# T11-MIDITheremin.net
KiCad netlist of a schematic drawn in EAGLE
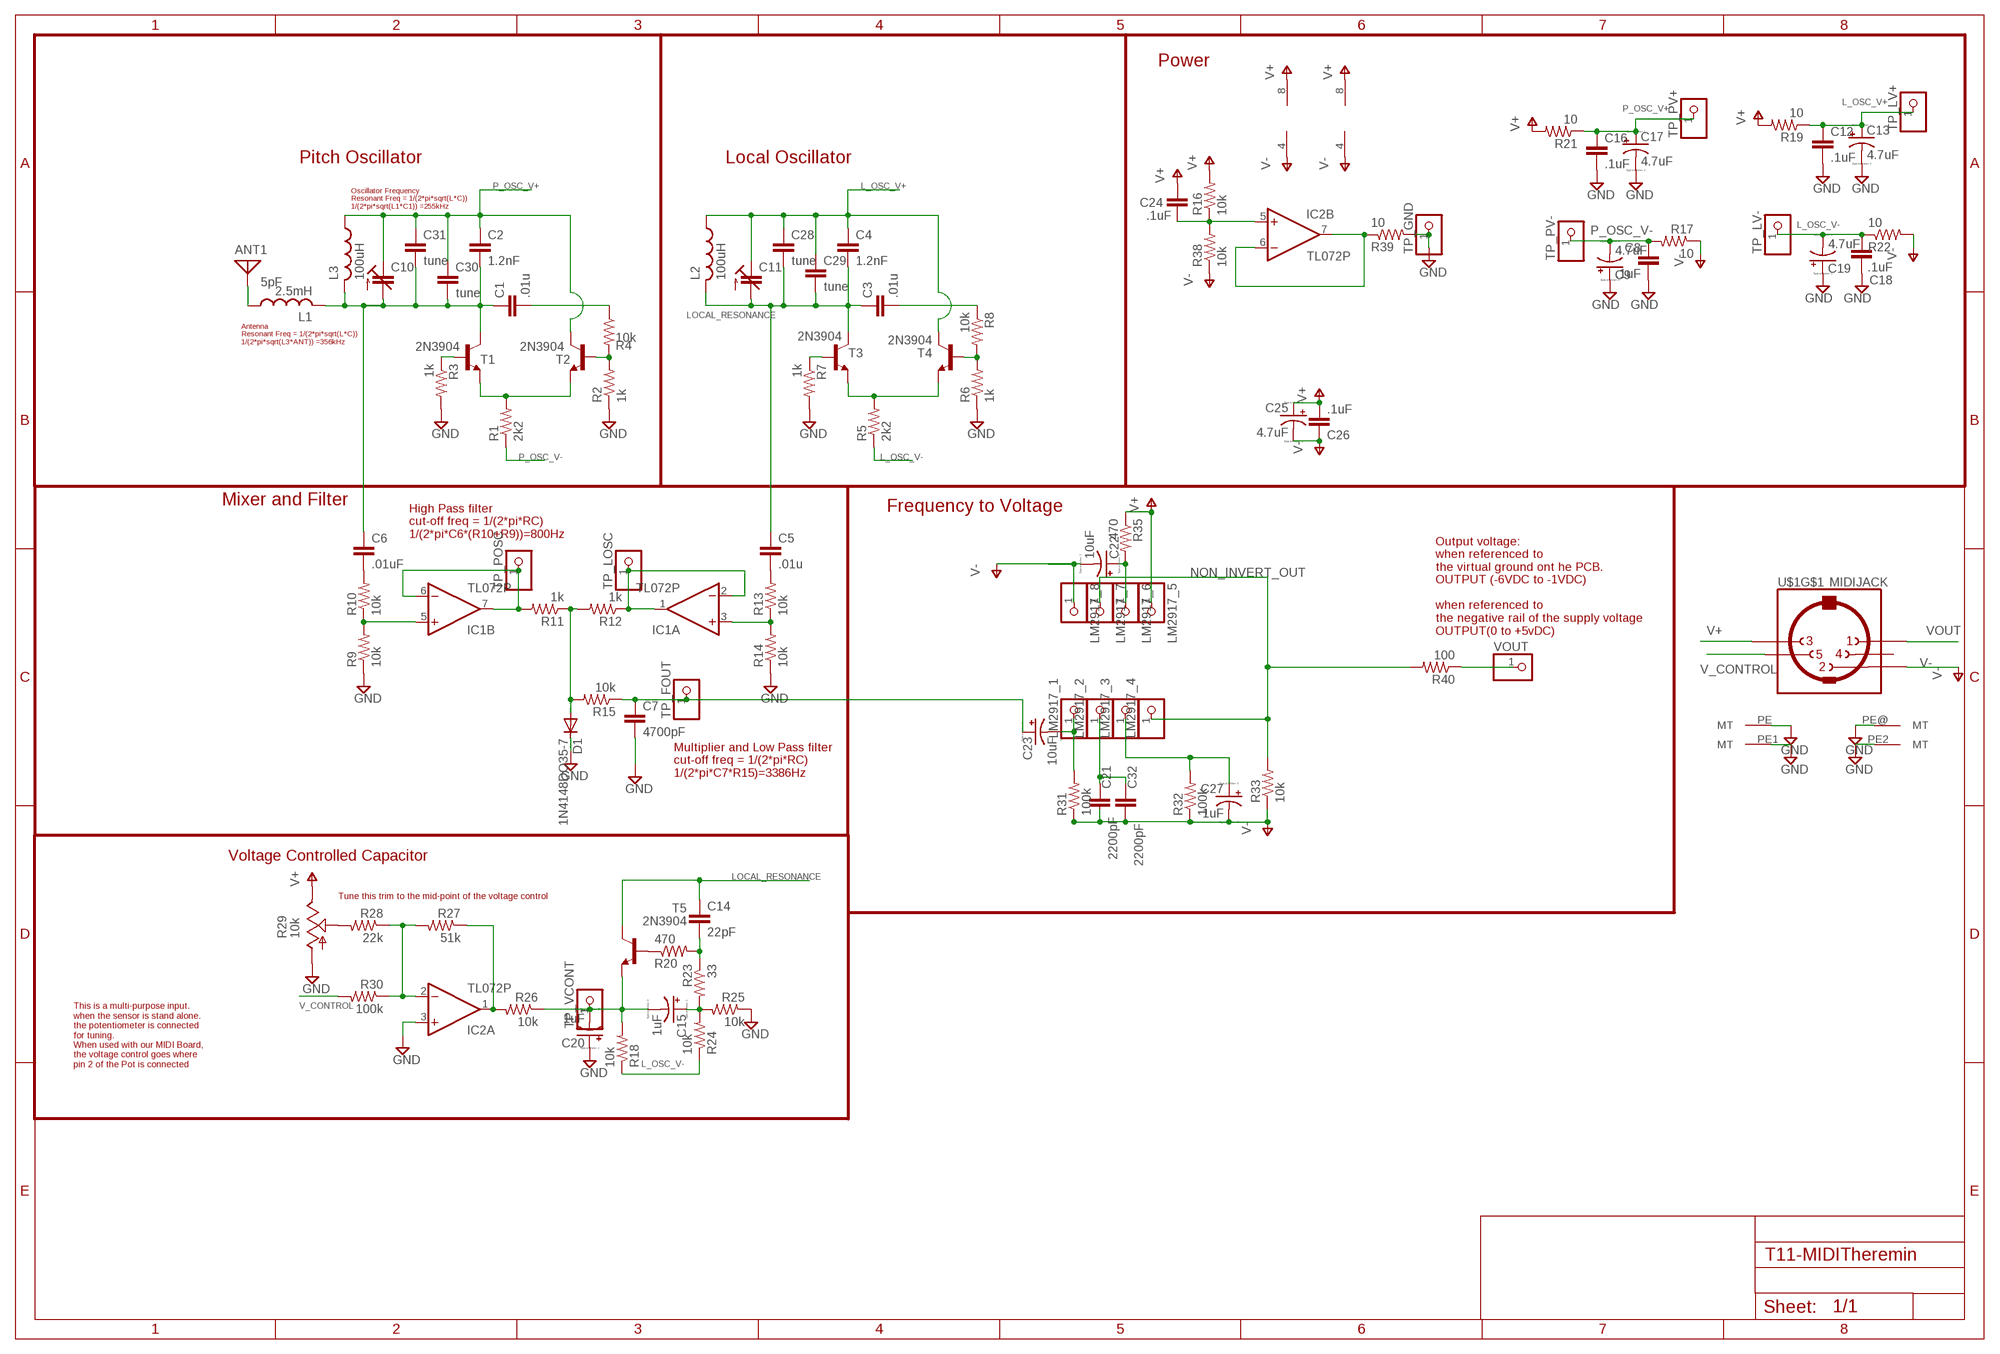
[diagram p0: schematic, sheet 1]

(export (version "E")
  (design (tool "Eeschema 10.0.6"))
  (components
    (comp (ref "ANT1")
      (value "5pF")
      (footprint "eagle-import:PAD-01")
      (libsource (lib "eagle-import") (part "ANTENNA"))
    )
    (comp (ref "C1")
      (value ".01u")
      (footprint "eagle-import:C050-025X075")
      (libsource (lib "eagle-import") (part "C-EU050-025X075"))
    )
    (comp (ref "C2")
      (value "1.2nF")
      (footprint "eagle-import:C050-025X075")
      (libsource (lib "eagle-import") (part "C-EU050-025X075"))
    )
    (comp (ref "C3")
      (value ".01u")
      (footprint "eagle-import:C050-025X075")
      (libsource (lib "eagle-import") (part "C-EU050-025X075"))
    )
    (comp (ref "C4")
      (value "1.2nF")
      (footprint "eagle-import:C050-025X075")
      (libsource (lib "eagle-import") (part "C-EU050-025X075"))
    )
    (comp (ref "C5")
      (value ".01u")
      (footprint "eagle-import:C050-025X075")
      (libsource (lib "eagle-import") (part "C-EU050-025X075"))
    )
    (comp (ref "C6")
      (value ".01uF")
      (footprint "eagle-import:C050-025X075")
      (libsource (lib "eagle-import") (part "C-EU050-025X075"))
    )
    (comp (ref "C7")
      (value "4700pF")
      (footprint "eagle-import:C050-025X075")
      (libsource (lib "eagle-import") (part "C-EU050-025X075"))
    )
    (comp (ref "C8")
      (value ".1uF")
      (footprint "eagle-import:C050-025X075")
      (libsource (lib "eagle-import") (part "C-EU050-025X075"))
    )
    (comp (ref "C9")
      (value "4.7uF")
      (footprint "eagle-import:E2,5-7")
      (libsource (lib "eagle-import") (part "CPOL-USE2.5-7"))
    )
    (comp (ref "C10")
      (value "C-TRIMM3040.427")
      (footprint "eagle-import:CTRIM3040.427")
      (libsource (lib "eagle-import") (part "C-TRIMM3040.427"))
    )
    (comp (ref "C11")
      (value "C-TRIMM3040.427")
      (footprint "eagle-import:CTRIM3040.427")
      (libsource (lib "eagle-import") (part "C-TRIMM3040.427"))
    )
    (comp (ref "C12")
      (value ".1uF")
      (footprint "eagle-import:C050-025X075")
      (libsource (lib "eagle-import") (part "C-EU050-025X075"))
    )
    (comp (ref "C13")
      (value "4.7uF")
      (footprint "eagle-import:E2,5-7")
      (libsource (lib "eagle-import") (part "CPOL-USE2.5-7"))
    )
    (comp (ref "C14")
      (value "22pF")
      (footprint "eagle-import:C050-025X075")
      (libsource (lib "eagle-import") (part "C-EU050-025X075"))
    )
    (comp (ref "C15")
      (value "1uF")
      (footprint "eagle-import:E2,5-7")
      (libsource (lib "eagle-import") (part "CPOL-USE2.5-7"))
    )
    (comp (ref "C16")
      (value ".1uF")
      (footprint "eagle-import:C050-025X075")
      (libsource (lib "eagle-import") (part "C-EU050-025X075"))
    )
    (comp (ref "C17")
      (value "4.7uF")
      (footprint "eagle-import:E2,5-7")
      (libsource (lib "eagle-import") (part "CPOL-USE2.5-7"))
    )
    (comp (ref "C18")
      (value ".1uF")
      (footprint "eagle-import:C050-025X075")
      (libsource (lib "eagle-import") (part "C-EU050-025X075"))
    )
    (comp (ref "C19")
      (value "4.7uF")
      (footprint "eagle-import:E2,5-7")
      (libsource (lib "eagle-import") (part "CPOL-USE2.5-7"))
    )
    (comp (ref "C20")
      (value "1uF")
      (footprint "eagle-import:E2,5-7")
      (libsource (lib "eagle-import") (part "CPOL-USE2.5-7"))
    )
    (comp (ref "C21")
      (value "2200pF")
      (footprint "eagle-import:C050-025X075")
      (libsource (lib "eagle-import") (part "C-EU050-025X075"))
    )
    (comp (ref "C22")
      (value "10uF")
      (footprint "eagle-import:E2,5-7")
      (libsource (lib "eagle-import") (part "CPOL-USE2.5-7"))
    )
    (comp (ref "C23")
      (value "10uF")
      (footprint "eagle-import:E2,5-7")
      (libsource (lib "eagle-import") (part "CPOL-USE2.5-7"))
    )
    (comp (ref "C24")
      (value ".1uF")
      (footprint "eagle-import:C050-025X075")
      (libsource (lib "eagle-import") (part "C-EU050-025X075"))
    )
    (comp (ref "C25")
      (value "4.7uF")
      (footprint "eagle-import:E2,5-7")
      (libsource (lib "eagle-import") (part "CPOL-USE2.5-7"))
    )
    (comp (ref "C26")
      (value ".1uF")
      (footprint "eagle-import:C050-025X075")
      (libsource (lib "eagle-import") (part "C-EU050-025X075"))
    )
    (comp (ref "C27")
      (value "1uF")
      (footprint "eagle-import:E2,5-7")
      (libsource (lib "eagle-import") (part "CPOL-USE2.5-7"))
    )
    (comp (ref "C28")
      (value "tune")
      (footprint "eagle-import:C050-025X075")
      (libsource (lib "eagle-import") (part "C-EU050-025X075"))
    )
    (comp (ref "C29")
      (value "tune")
      (footprint "eagle-import:C050-025X075")
      (libsource (lib "eagle-import") (part "C-EU050-025X075"))
    )
    (comp (ref "C30")
      (value "tune")
      (footprint "eagle-import:C050-025X075")
      (libsource (lib "eagle-import") (part "C-EU050-025X075"))
    )
    (comp (ref "C31")
      (value "tune")
      (footprint "eagle-import:C050-025X075")
      (libsource (lib "eagle-import") (part "C-EU050-025X075"))
    )
    (comp (ref "C32")
      (value "2200pF")
      (footprint "eagle-import:C050-025X075")
      (libsource (lib "eagle-import") (part "C-EU050-025X075"))
    )
    (comp (ref "D1")
      (value "1N4148DO35-7")
      (footprint "eagle-import:DO35-7")
      (libsource (lib "eagle-import") (part "1N4148DO35-7"))
    )
    (comp (ref "IC1")
      (value "TL072P")
      (footprint "eagle-import:DIL08")
      (libsource (lib "eagle-import") (part "TL072P"))
    )
    (comp (ref "IC2")
      (value "TL072P")
      (footprint "eagle-import:DIL08")
      (libsource (lib "eagle-import") (part "TL072P"))
    )
    (comp (ref "L1")
      (value "2.5mH")
      (footprint "eagle-import:0207_5V")
      (libsource (lib "eagle-import") (part "L-US0207/5V"))
    )
    (comp (ref "L2")
      (value "100uH")
      (footprint "eagle-import:0207_5V")
      (libsource (lib "eagle-import") (part "L-US0207/5V"))
    )
    (comp (ref "L3")
      (value "100uH")
      (footprint "eagle-import:0207_5V")
      (libsource (lib "eagle-import") (part "L-US0207/5V"))
    )
    (comp (ref "LM2917_1")
      (value "PINHD-1X1")
      (footprint "eagle-import:1X01")
      (libsource (lib "eagle-import") (part "PINHD-1X1"))
    )
    (comp (ref "LM2917_2")
      (value "PINHD-1X1")
      (footprint "eagle-import:1X01")
      (libsource (lib "eagle-import") (part "PINHD-1X1"))
    )
    (comp (ref "LM2917_3")
      (value "PINHD-1X1")
      (footprint "eagle-import:1X01")
      (libsource (lib "eagle-import") (part "PINHD-1X1"))
    )
    (comp (ref "LM2917_4")
      (value "PINHD-1X1")
      (footprint "eagle-import:1X01")
      (libsource (lib "eagle-import") (part "PINHD-1X1"))
    )
    (comp (ref "LM2917_5")
      (value "PINHD-1X1")
      (footprint "eagle-import:1X01")
      (libsource (lib "eagle-import") (part "PINHD-1X1"))
    )
    (comp (ref "LM2917_6")
      (value "PINHD-1X1")
      (footprint "eagle-import:1X01")
      (libsource (lib "eagle-import") (part "PINHD-1X1"))
    )
    (comp (ref "LM2917_7")
      (value "PINHD-1X1")
      (footprint "eagle-import:1X01")
      (libsource (lib "eagle-import") (part "PINHD-1X1"))
    )
    (comp (ref "LM2917_8")
      (value "PINHD-1X1")
      (footprint "eagle-import:1X01")
      (libsource (lib "eagle-import") (part "PINHD-1X1"))
    )
    (comp (ref "R1")
      (value "2k2")
      (footprint "eagle-import:0411V")
      (libsource (lib "eagle-import") (part "resistor_R-US_0411/3V"))
    )
    (comp (ref "R2")
      (value "1k")
      (footprint "eagle-import:0411V")
      (libsource (lib "eagle-import") (part "resistor_R-US_0411/3V"))
    )
    (comp (ref "R3")
      (value "1k")
      (footprint "eagle-import:0411V")
      (libsource (lib "eagle-import") (part "resistor_R-US_0411/3V"))
    )
    (comp (ref "R4")
      (value "10k")
      (footprint "eagle-import:0411V")
      (libsource (lib "eagle-import") (part "resistor_R-US_0411/3V"))
    )
    (comp (ref "R5")
      (value "2k2")
      (footprint "eagle-import:0411V")
      (libsource (lib "eagle-import") (part "resistor_R-US_0411/3V"))
    )
    (comp (ref "R6")
      (value "1k")
      (footprint "eagle-import:0411V")
      (libsource (lib "eagle-import") (part "resistor_R-US_0411/3V"))
    )
    (comp (ref "R7")
      (value "1k")
      (footprint "eagle-import:0411V")
      (libsource (lib "eagle-import") (part "resistor_R-US_0411/3V"))
    )
    (comp (ref "R8")
      (value "10k")
      (footprint "eagle-import:0411V")
      (libsource (lib "eagle-import") (part "resistor_R-US_0411/3V"))
    )
    (comp (ref "R9")
      (value "10k")
      (footprint "eagle-import:0411V")
      (libsource (lib "eagle-import") (part "resistor_R-US_0411/3V"))
    )
    (comp (ref "R10")
      (value "10k")
      (footprint "eagle-import:0411V")
      (libsource (lib "eagle-import") (part "resistor_R-US_0411/3V"))
    )
    (comp (ref "R11")
      (value "1k")
      (footprint "eagle-import:0411V")
      (libsource (lib "eagle-import") (part "resistor_R-US_0411/3V"))
    )
    (comp (ref "R12")
      (value "1k")
      (footprint "eagle-import:0411V")
      (libsource (lib "eagle-import") (part "resistor_R-US_0411/3V"))
    )
    (comp (ref "R13")
      (value "10k")
      (footprint "eagle-import:0411V")
      (libsource (lib "eagle-import") (part "resistor_R-US_0411/3V"))
    )
    (comp (ref "R14")
      (value "10k")
      (footprint "eagle-import:0411V")
      (libsource (lib "eagle-import") (part "resistor_R-US_0411/3V"))
    )
    (comp (ref "R15")
      (value "10k")
      (footprint "eagle-import:0411V")
      (libsource (lib "eagle-import") (part "resistor_R-US_0411/3V"))
    )
    (comp (ref "R16")
      (value "10k")
      (footprint "eagle-import:0411V")
      (libsource (lib "eagle-import") (part "resistor_R-US_0411/3V"))
    )
    (comp (ref "R17")
      (value "10")
      (footprint "eagle-import:0411V")
      (libsource (lib "eagle-import") (part "resistor_R-US_0411/3V"))
    )
    (comp (ref "R18")
      (value "10k")
      (footprint "eagle-import:0411V")
      (libsource (lib "eagle-import") (part "resistor_R-US_0411/3V"))
    )
    (comp (ref "R19")
      (value "10")
      (footprint "eagle-import:0411V")
      (libsource (lib "eagle-import") (part "resistor_R-US_0411/3V"))
    )
    (comp (ref "R20")
      (value "470")
      (footprint "eagle-import:0411V")
      (libsource (lib "eagle-import") (part "resistor_R-US_0411/3V"))
    )
    (comp (ref "R21")
      (value "10")
      (footprint "eagle-import:0411V")
      (libsource (lib "eagle-import") (part "resistor_R-US_0411/3V"))
    )
    (comp (ref "R22")
      (value "10")
      (footprint "eagle-import:0411V")
      (libsource (lib "eagle-import") (part "resistor_R-US_0411/3V"))
    )
    (comp (ref "R23")
      (value "33")
      (footprint "eagle-import:0411V")
      (libsource (lib "eagle-import") (part "resistor_R-US_0411/3V"))
    )
    (comp (ref "R24")
      (value "10k")
      (footprint "eagle-import:0411V")
      (libsource (lib "eagle-import") (part "resistor_R-US_0411/3V"))
    )
    (comp (ref "R25")
      (value "10k")
      (footprint "eagle-import:0411V")
      (libsource (lib "eagle-import") (part "resistor_R-US_0411/3V"))
    )
    (comp (ref "R26")
      (value "10k")
      (footprint "eagle-import:0411V")
      (libsource (lib "eagle-import") (part "resistor_R-US_0411/3V"))
    )
    (comp (ref "R27")
      (value "51k")
      (footprint "eagle-import:0411V")
      (libsource (lib "eagle-import") (part "resistor_R-US_0411/3V"))
    )
    (comp (ref "R28")
      (value "22k")
      (footprint "eagle-import:0411V")
      (libsource (lib "eagle-import") (part "resistor_R-US_0411/3V"))
    )
    (comp (ref "R29")
      (value "10k")
      (footprint "eagle-import:B64Y")
      (libsource (lib "eagle-import") (part "TRIM_US-B64Y"))
    )
    (comp (ref "R30")
      (value "100k")
      (footprint "eagle-import:0411V")
      (libsource (lib "eagle-import") (part "resistor_R-US_0411/3V"))
    )
    (comp (ref "R31")
      (value "100k")
      (footprint "eagle-import:0411V")
      (libsource (lib "eagle-import") (part "R-US_0411/3V"))
    )
    (comp (ref "R32")
      (value "100k")
      (footprint "eagle-import:0411V")
      (libsource (lib "eagle-import") (part "R-US_0411/3V"))
    )
    (comp (ref "R33")
      (value "10k")
      (footprint "eagle-import:0411V")
      (libsource (lib "eagle-import") (part "R-US_0411/3V"))
    )
    (comp (ref "R35")
      (value "470")
      (footprint "eagle-import:0411V")
      (libsource (lib "eagle-import") (part "R-US_0411/3V"))
    )
    (comp (ref "R38")
      (value "10k")
      (footprint "eagle-import:0411V")
      (libsource (lib "eagle-import") (part "resistor_R-US_0411/3V"))
    )
    (comp (ref "R39")
      (value "10")
      (footprint "eagle-import:0411V")
      (libsource (lib "eagle-import") (part "resistor_R-US_0411/3V"))
    )
    (comp (ref "R40")
      (value "100")
      (footprint "eagle-import:0411V")
      (libsource (lib "eagle-import") (part "R-US_0411/3V"))
    )
    (comp (ref "T1")
      (value "2N3904")
      (footprint "eagle-import:TO92")
      (libsource (lib "eagle-import") (part "2N3904"))
    )
    (comp (ref "T2")
      (value "2N3904")
      (footprint "eagle-import:TO92")
      (libsource (lib "eagle-import") (part "2N3904"))
    )
    (comp (ref "T3")
      (value "2N3904")
      (footprint "eagle-import:TO92")
      (libsource (lib "eagle-import") (part "2N3904"))
    )
    (comp (ref "T4")
      (value "2N3904")
      (footprint "eagle-import:TO92")
      (libsource (lib "eagle-import") (part "2N3904"))
    )
    (comp (ref "T5")
      (value "2N3904")
      (footprint "eagle-import:TO92")
      (libsource (lib "eagle-import") (part "2N3904"))
    )
    (comp (ref "TP_FOUT")
      (value "PINHD-1X1")
      (footprint "eagle-import:1X01")
      (libsource (lib "eagle-import") (part "PINHD-1X1"))
    )
    (comp (ref "TP_GND")
      (value "PINHD-1X1")
      (footprint "eagle-import:1X01")
      (libsource (lib "eagle-import") (part "PINHD-1X1"))
    )
    (comp (ref "TP_LOSC")
      (value "PINHD-1X1")
      (footprint "eagle-import:1X01")
      (libsource (lib "eagle-import") (part "PINHD-1X1"))
    )
    (comp (ref "TP_LV+")
      (value "PINHD-1X1")
      (footprint "eagle-import:1X01")
      (libsource (lib "eagle-import") (part "PINHD-1X1"))
    )
    (comp (ref "TP_LV-")
      (value "PINHD-1X1")
      (footprint "eagle-import:1X01")
      (libsource (lib "eagle-import") (part "PINHD-1X1"))
    )
    (comp (ref "TP_POSC")
      (value "PINHD-1X1")
      (footprint "eagle-import:1X01")
      (libsource (lib "eagle-import") (part "PINHD-1X1"))
    )
    (comp (ref "TP_PV+")
      (value "PINHD-1X1")
      (footprint "eagle-import:1X01")
      (libsource (lib "eagle-import") (part "PINHD-1X1"))
    )
    (comp (ref "TP_PV-")
      (value "PINHD-1X1")
      (footprint "eagle-import:1X01")
      (libsource (lib "eagle-import") (part "PINHD-1X1"))
    )
    (comp (ref "TP_VCONT")
      (value "PINHD-1X1")
      (footprint "eagle-import:1X01")
      (libsource (lib "eagle-import") (part "PINHD-1X1"))
    )
    (comp (ref "U$1")
      (value "MIDIJACK")
      (footprint "eagle-import:CP-2350")
      (libsource (lib "eagle-import") (part "MIDIJACK"))
    )
    (comp (ref "VOUT")
      (value "PINHD-1X1")
      (footprint "eagle-import:1X01")
      (libsource (lib "eagle-import") (part "PINHD-1X1"))
    )
  )
  (nets
    (net (code "1") (name "/LOCAL_RESONANCE") (class "Default")
      (node (ref "C11") (pin "2") (pinfunction "A_2") (pintype "passive"))
      (node (ref "C14") (pin "1") (pinfunction "1_1") (pintype "passive"))
      (node (ref "C28") (pin "2") (pinfunction "2_2") (pintype "passive"))
      (node (ref "C29") (pin "2") (pinfunction "2_2") (pintype "passive"))
      (node (ref "C3") (pin "1") (pinfunction "1_1") (pintype "passive"))
      (node (ref "C4") (pin "2") (pinfunction "2_2") (pintype "passive"))
      (node (ref "C5") (pin "1") (pinfunction "1_1") (pintype "passive"))
      (node (ref "L2") (pin "2") (pinfunction "2_2") (pintype "passive"))
      (node (ref "T3") (pin "1") (pinfunction "C_1") (pintype "passive"))
      (node (ref "T5") (pin "1") (pinfunction "C_1") (pintype "passive"))
    )
    (net (code "2") (name "/L_OSC_V+") (class "Default")
      (node (ref "C11") (pin "1A") (pinfunction "E_1A") (pintype "passive"))
      (node (ref "C12") (pin "1") (pinfunction "1_1") (pintype "passive"))
      (node (ref "C13") (pin "+") (pinfunction "+_+") (pintype "passive"))
      (node (ref "C28") (pin "1") (pinfunction "1_1") (pintype "passive"))
      (node (ref "C29") (pin "1") (pinfunction "1_1") (pintype "passive"))
      (node (ref "C4") (pin "1") (pinfunction "1_1") (pintype "passive"))
      (node (ref "L2") (pin "1") (pinfunction "1_1") (pintype "passive"))
      (node (ref "R19") (pin "1") (pinfunction "1_1") (pintype "passive"))
      (node (ref "T4") (pin "1") (pinfunction "C_1") (pintype "passive"))
      (node (ref "TP_LV+") (pin "1") (pinfunction "1_1") (pintype "passive"))
    )
    (net (code "3") (name "/L_OSC_V-") (class "Default")
      (node (ref "C18") (pin "1") (pinfunction "1_1") (pintype "passive"))
      (node (ref "C19") (pin "-") (pinfunction "-_-") (pintype "passive"))
      (node (ref "R18") (pin "1") (pinfunction "1_1") (pintype "passive"))
      (node (ref "R22") (pin "1") (pinfunction "1_1") (pintype "passive"))
      (node (ref "R24") (pin "1") (pinfunction "1_1") (pintype "passive"))
      (node (ref "R5") (pin "1") (pinfunction "1_1") (pintype "passive"))
      (node (ref "TP_LV-") (pin "1") (pinfunction "1_1") (pintype "passive"))
    )
    (net (code "4") (name "/NON_INVERT_OUT") (class "Default")
      (node (ref "LM2917_4") (pin "1") (pinfunction "1_1") (pintype "passive"))
      (node (ref "LM2917_7") (pin "1") (pinfunction "1_1") (pintype "passive"))
      (node (ref "R33") (pin "2") (pinfunction "2_2") (pintype "passive"))
      (node (ref "R40") (pin "2") (pinfunction "2_2") (pintype "passive"))
    )
    (net (code "5") (name "/P_OSC_V+") (class "Default")
      (node (ref "C10") (pin "1A") (pinfunction "E_1A") (pintype "passive"))
      (node (ref "C16") (pin "1") (pinfunction "1_1") (pintype "passive"))
      (node (ref "C17") (pin "+") (pinfunction "+_+") (pintype "passive"))
      (node (ref "C2") (pin "1") (pinfunction "1_1") (pintype "passive"))
      (node (ref "C30") (pin "1") (pinfunction "1_1") (pintype "passive"))
      (node (ref "C31") (pin "1") (pinfunction "1_1") (pintype "passive"))
      (node (ref "L3") (pin "1") (pinfunction "1_1") (pintype "passive"))
      (node (ref "R21") (pin "1") (pinfunction "1_1") (pintype "passive"))
      (node (ref "T2") (pin "1") (pinfunction "C_1") (pintype "passive"))
      (node (ref "TP_PV+") (pin "1") (pinfunction "1_1") (pintype "passive"))
    )
    (net (code "6") (name "/P_OSC_V-") (class "Default")
      (node (ref "C8") (pin "1") (pinfunction "1_1") (pintype "passive"))
      (node (ref "C9") (pin "-") (pinfunction "-_-") (pintype "passive"))
      (node (ref "R1") (pin "1") (pinfunction "1_1") (pintype "passive"))
      (node (ref "R17") (pin "2") (pinfunction "2_2") (pintype "passive"))
      (node (ref "TP_PV-") (pin "1") (pinfunction "1_1") (pintype "passive"))
    )
    (net (code "7") (name "/VOUT") (class "Default")
      (node (ref "R40") (pin "1") (pinfunction "1_1") (pintype "passive"))
      (node (ref "U$1") (pin "1") (pinfunction "1_1") (pintype "passive"))
      (node (ref "VOUT") (pin "1") (pinfunction "1_1") (pintype "passive"))
    )
    (net (code "8") (name "/V_CONTROL") (class "Default")
      (node (ref "R30") (pin "2") (pinfunction "2_2") (pintype "passive"))
      (node (ref "U$1") (pin "5") (pinfunction "5_5") (pintype "passive"))
    )
    (net (code "9") (name "GND") (class "Default")
      (node (ref "C12") (pin "2") (pinfunction "2_2") (pintype "passive"))
      (node (ref "C13") (pin "-") (pinfunction "-_-") (pintype "passive"))
      (node (ref "C16") (pin "2") (pinfunction "2_2") (pintype "passive"))
      (node (ref "C17") (pin "-") (pinfunction "-_-") (pintype "passive"))
      (node (ref "C18") (pin "2") (pinfunction "2_2") (pintype "passive"))
      (node (ref "C19") (pin "+") (pinfunction "+_+") (pintype "passive"))
      (node (ref "C20") (pin "+") (pinfunction "+_+") (pintype "passive"))
      (node (ref "C7") (pin "2") (pinfunction "2_2") (pintype "passive"))
      (node (ref "C8") (pin "2") (pinfunction "2_2") (pintype "passive"))
      (node (ref "C9") (pin "+") (pinfunction "+_+") (pintype "passive"))
      (node (ref "D1") (pin "C") (pinfunction "C_C") (pintype "passive"))
      (node (ref "IC2") (pin "3") (pinfunction "+IN_3") (pintype "input"))
      (node (ref "R14") (pin "1") (pinfunction "1_1") (pintype "passive"))
      (node (ref "R2") (pin "1") (pinfunction "1_1") (pintype "passive"))
      (node (ref "R25") (pin "1") (pinfunction "1_1") (pintype "passive"))
      (node (ref "R29") (pin "A") (pinfunction "A_A") (pintype "passive"))
      (node (ref "R3") (pin "2") (pinfunction "2_2") (pintype "passive"))
      (node (ref "R39") (pin "2") (pinfunction "2_2") (pintype "passive"))
      (node (ref "R6") (pin "1") (pinfunction "1_1") (pintype "passive"))
      (node (ref "R7") (pin "2") (pinfunction "2_2") (pintype "passive"))
      (node (ref "R9") (pin "1") (pinfunction "1_1") (pintype "passive"))
      (node (ref "TP_GND") (pin "1") (pinfunction "1_1") (pintype "passive"))
      (node (ref "U$1") (pin "PE") (pinfunction "MT_PE") (pintype "passive"))
      (node (ref "U$1") (pin "PE1") (pinfunction "MT_PE1") (pintype "passive"))
      (node (ref "U$1") (pin "PE2") (pinfunction "MT_PE2") (pintype "passive"))
      (node (ref "U$1") (pin "PE@") (pinfunction "MT_PE@") (pintype "passive"))
    )
    (net (code "10") (name "Net-(ANT1-Pad1)") (class "Default")
      (node (ref "ANT1") (pin "1") (pinfunction "1_1") (pintype "output"))
      (node (ref "L1") (pin "1") (pinfunction "1_1") (pintype "passive"))
    )
    (net (code "11") (name "Net-(C1-Pad2)") (class "Default")
      (node (ref "C1") (pin "2") (pinfunction "2_2") (pintype "passive"))
      (node (ref "R4") (pin "1") (pinfunction "1_1") (pintype "passive"))
    )
    (net (code "12") (name "Net-(C3-Pad2)") (class "Default")
      (node (ref "C3") (pin "2") (pinfunction "2_2") (pintype "passive"))
      (node (ref "R8") (pin "1") (pinfunction "1_1") (pintype "passive"))
    )
    (net (code "13") (name "Net-(C5-Pad2)") (class "Default")
      (node (ref "C5") (pin "2") (pinfunction "2_2") (pintype "passive"))
      (node (ref "R13") (pin "2") (pinfunction "2_2") (pintype "passive"))
    )
    (net (code "14") (name "Net-(C6-Pad2)") (class "Default")
      (node (ref "C6") (pin "2") (pinfunction "2_2") (pintype "passive"))
      (node (ref "R10") (pin "2") (pinfunction "2_2") (pintype "passive"))
    )
    (net (code "15") (name "Net-(C10-A)") (class "Default")
      (node (ref "C1") (pin "1") (pinfunction "1_1") (pintype "passive"))
      (node (ref "C10") (pin "2") (pinfunction "A_2") (pintype "passive"))
      (node (ref "C2") (pin "2") (pinfunction "2_2") (pintype "passive"))
      (node (ref "C30") (pin "2") (pinfunction "2_2") (pintype "passive"))
      (node (ref "C31") (pin "2") (pinfunction "2_2") (pintype "passive"))
      (node (ref "C6") (pin "1") (pinfunction "1_1") (pintype "passive"))
      (node (ref "L1") (pin "2") (pinfunction "2_2") (pintype "passive"))
      (node (ref "L3") (pin "2") (pinfunction "2_2") (pintype "passive"))
      (node (ref "T1") (pin "1") (pinfunction "C_1") (pintype "passive"))
    )
    (net (code "16") (name "Net-(C14-Pad2)") (class "Default")
      (node (ref "C14") (pin "2") (pinfunction "2_2") (pintype "passive"))
      (node (ref "R20") (pin "2") (pinfunction "2_2") (pintype "passive"))
      (node (ref "R23") (pin "1") (pinfunction "1_1") (pintype "passive"))
    )
    (net (code "17") (name "Net-(C15-Pad+)") (class "Default")
      (node (ref "C15") (pin "+") (pinfunction "+_+") (pintype "passive"))
      (node (ref "R23") (pin "2") (pinfunction "2_2") (pintype "passive"))
      (node (ref "R24") (pin "2") (pinfunction "2_2") (pintype "passive"))
      (node (ref "R25") (pin "2") (pinfunction "2_2") (pintype "passive"))
    )
    (net (code "18") (name "Net-(C21-Pad1)") (class "Default")
      (node (ref "C21") (pin "1") (pinfunction "1_1") (pintype "passive"))
      (node (ref "C32") (pin "1") (pinfunction "1_1") (pintype "passive"))
      (node (ref "LM2917_2") (pin "1") (pinfunction "1_1") (pintype "passive"))
    )
    (net (code "19") (name "Net-(C22-Pad+)") (class "Default")
      (node (ref "C22") (pin "+") (pinfunction "+_+") (pintype "passive"))
      (node (ref "LM2917_6") (pin "1") (pinfunction "1_1") (pintype "passive"))
      (node (ref "R35") (pin "2") (pinfunction "2_2") (pintype "passive"))
    )
    (net (code "20") (name "Net-(C23-Pad+)") (class "Default")
      (node (ref "C23") (pin "+") (pinfunction "+_+") (pintype "passive"))
      (node (ref "C7") (pin "1") (pinfunction "1_1") (pintype "passive"))
      (node (ref "R15") (pin "1") (pinfunction "1_1") (pintype "passive"))
      (node (ref "TP_FOUT") (pin "1") (pinfunction "1_1") (pintype "passive"))
    )
    (net (code "21") (name "Net-(C23-Pad-)") (class "Default")
      (node (ref "C23") (pin "-") (pinfunction "-_-") (pintype "passive"))
      (node (ref "LM2917_1") (pin "1") (pinfunction "1_1") (pintype "passive"))
      (node (ref "R31") (pin "2") (pinfunction "2_2") (pintype "passive"))
    )
    (net (code "22") (name "Net-(C27-Pad+)") (class "Default")
      (node (ref "C27") (pin "+") (pinfunction "+_+") (pintype "passive"))
      (node (ref "LM2917_3") (pin "1") (pinfunction "1_1") (pintype "passive"))
      (node (ref "R32") (pin "2") (pinfunction "2_2") (pintype "passive"))
    )
    (net (code "23") (name "Net-(D1-PadA)") (class "Default")
      (node (ref "D1") (pin "A") (pinfunction "A_A") (pintype "passive"))
      (node (ref "R11") (pin "1") (pinfunction "1_1") (pintype "passive"))
      (node (ref "R12") (pin "2") (pinfunction "2_2") (pintype "passive"))
      (node (ref "R15") (pin "2") (pinfunction "2_2") (pintype "passive"))
    )
    (net (code "24") (name "Net-(IC1A-+IN)") (class "Default")
      (node (ref "IC1") (pin "3") (pinfunction "+IN_3") (pintype "input"))
      (node (ref "R13") (pin "1") (pinfunction "1_1") (pintype "passive"))
      (node (ref "R14") (pin "2") (pinfunction "2_2") (pintype "passive"))
    )
    (net (code "25") (name "Net-(IC1A--IN)") (class "Default")
      (node (ref "IC1") (pin "1") (pinfunction "OUT_1") (pintype "output"))
      (node (ref "IC1") (pin "2") (pinfunction "-IN_2") (pintype "input"))
      (node (ref "R12") (pin "1") (pinfunction "1_1") (pintype "passive"))
      (node (ref "TP_LOSC") (pin "1") (pinfunction "1_1") (pintype "passive"))
    )
    (net (code "26") (name "Net-(IC1B-+IN)") (class "Default")
      (node (ref "IC1") (pin "5") (pinfunction "+IN_5") (pintype "input"))
      (node (ref "R10") (pin "1") (pinfunction "1_1") (pintype "passive"))
      (node (ref "R9") (pin "2") (pinfunction "2_2") (pintype "passive"))
    )
    (net (code "27") (name "Net-(IC1B--IN)") (class "Default")
      (node (ref "IC1") (pin "6") (pinfunction "-IN_6") (pintype "input"))
      (node (ref "IC1") (pin "7") (pinfunction "OUT_7") (pintype "output"))
      (node (ref "R11") (pin "2") (pinfunction "2_2") (pintype "passive"))
      (node (ref "TP_POSC") (pin "1") (pinfunction "1_1") (pintype "passive"))
    )
    (net (code "28") (name "Net-(IC2A--IN)") (class "Default")
      (node (ref "IC2") (pin "2") (pinfunction "-IN_2") (pintype "input"))
      (node (ref "R27") (pin "2") (pinfunction "2_2") (pintype "passive"))
      (node (ref "R28") (pin "1") (pinfunction "1_1") (pintype "passive"))
      (node (ref "R30") (pin "1") (pinfunction "1_1") (pintype "passive"))
    )
    (net (code "29") (name "Net-(IC2A-OUT)") (class "Default")
      (node (ref "IC2") (pin "1") (pinfunction "OUT_1") (pintype "output"))
      (node (ref "R26") (pin "2") (pinfunction "2_2") (pintype "passive"))
      (node (ref "R27") (pin "1") (pinfunction "1_1") (pintype "passive"))
    )
    (net (code "30") (name "Net-(IC2B-+IN)") (class "Default")
      (node (ref "C24") (pin "2") (pinfunction "2_2") (pintype "passive"))
      (node (ref "IC2") (pin "5") (pinfunction "+IN_5") (pintype "input"))
      (node (ref "R16") (pin "1") (pinfunction "1_1") (pintype "passive"))
      (node (ref "R38") (pin "2") (pinfunction "2_2") (pintype "passive"))
    )
    (net (code "31") (name "Net-(IC2B--IN)") (class "Default")
      (node (ref "IC2") (pin "6") (pinfunction "-IN_6") (pintype "input"))
      (node (ref "IC2") (pin "7") (pinfunction "OUT_7") (pintype "output"))
      (node (ref "R39") (pin "1") (pinfunction "1_1") (pintype "passive"))
    )
    (net (code "32") (name "Net-(R28-Pad2)") (class "Default")
      (node (ref "R28") (pin "2") (pinfunction "2_2") (pintype "passive"))
      (node (ref "R29") (pin "S") (pinfunction "S_S") (pintype "passive"))
    )
    (net (code "33") (name "Net-(T1-B)") (class "Default")
      (node (ref "R3") (pin "1") (pinfunction "1_1") (pintype "passive"))
      (node (ref "T1") (pin "2") (pinfunction "B_2") (pintype "passive"))
    )
    (net (code "34") (name "Net-(T1-E)") (class "Default")
      (node (ref "R1") (pin "2") (pinfunction "2_2") (pintype "passive"))
      (node (ref "T1") (pin "3") (pinfunction "E_3") (pintype "passive"))
      (node (ref "T2") (pin "3") (pinfunction "E_3") (pintype "passive"))
    )
    (net (code "35") (name "Net-(T2-B)") (class "Default")
      (node (ref "R2") (pin "2") (pinfunction "2_2") (pintype "passive"))
      (node (ref "R4") (pin "2") (pinfunction "2_2") (pintype "passive"))
      (node (ref "T2") (pin "2") (pinfunction "B_2") (pintype "passive"))
    )
    (net (code "36") (name "Net-(T3-B)") (class "Default")
      (node (ref "R7") (pin "1") (pinfunction "1_1") (pintype "passive"))
      (node (ref "T3") (pin "2") (pinfunction "B_2") (pintype "passive"))
    )
    (net (code "37") (name "Net-(T3-E)") (class "Default")
      (node (ref "R5") (pin "2") (pinfunction "2_2") (pintype "passive"))
      (node (ref "T3") (pin "3") (pinfunction "E_3") (pintype "passive"))
      (node (ref "T4") (pin "3") (pinfunction "E_3") (pintype "passive"))
    )
    (net (code "38") (name "Net-(T4-B)") (class "Default")
      (node (ref "R6") (pin "2") (pinfunction "2_2") (pintype "passive"))
      (node (ref "R8") (pin "2") (pinfunction "2_2") (pintype "passive"))
      (node (ref "T4") (pin "2") (pinfunction "B_2") (pintype "passive"))
    )
    (net (code "39") (name "Net-(T5-B)") (class "Default")
      (node (ref "R20") (pin "1") (pinfunction "1_1") (pintype "passive"))
      (node (ref "T5") (pin "2") (pinfunction "B_2") (pintype "passive"))
    )
    (net (code "40") (name "Net-(T5-E)") (class "Default")
      (node (ref "C15") (pin "-") (pinfunction "-_-") (pintype "passive"))
      (node (ref "C20") (pin "-") (pinfunction "-_-") (pintype "passive"))
      (node (ref "R18") (pin "2") (pinfunction "2_2") (pintype "passive"))
      (node (ref "R26") (pin "1") (pinfunction "1_1") (pintype "passive"))
      (node (ref "T5") (pin "3") (pinfunction "E_3") (pintype "passive"))
      (node (ref "TP_VCONT") (pin "1") (pinfunction "1_1") (pintype "passive"))
    )
    (net (code "41") (name "V+") (class "Default")
      (node (ref "C24") (pin "1") (pinfunction "1_1") (pintype "passive"))
      (node (ref "C25") (pin "+") (pinfunction "+_+") (pintype "passive"))
      (node (ref "C26") (pin "2") (pinfunction "2_2") (pintype "passive"))
      (node (ref "IC1") (pin "8") (pinfunction "V+_8") (pintype "power_in"))
      (node (ref "IC2") (pin "8") (pinfunction "V+_8") (pintype "power_in"))
      (node (ref "LM2917_5") (pin "1") (pinfunction "1_1") (pintype "passive"))
      (node (ref "R16") (pin "2") (pinfunction "2_2") (pintype "passive"))
      (node (ref "R19") (pin "2") (pinfunction "2_2") (pintype "passive"))
      (node (ref "R21") (pin "2") (pinfunction "2_2") (pintype "passive"))
      (node (ref "R29") (pin "E") (pinfunction "E_E") (pintype "passive"))
      (node (ref "R35") (pin "1") (pinfunction "1_1") (pintype "passive"))
      (node (ref "U$1") (pin "3") (pinfunction "3_3") (pintype "passive"))
    )
    (net (code "42") (name "V-") (class "Default")
      (node (ref "C21") (pin "2") (pinfunction "2_2") (pintype "passive"))
      (node (ref "C22") (pin "-") (pinfunction "-_-") (pintype "passive"))
      (node (ref "C25") (pin "-") (pinfunction "-_-") (pintype "passive"))
      (node (ref "C26") (pin "1") (pinfunction "1_1") (pintype "passive"))
      (node (ref "C27") (pin "-") (pinfunction "-_-") (pintype "passive"))
      (node (ref "C32") (pin "2") (pinfunction "2_2") (pintype "passive"))
      (node (ref "IC1") (pin "4") (pinfunction "V-_4") (pintype "power_in"))
      (node (ref "IC2") (pin "4") (pinfunction "V-_4") (pintype "power_in"))
      (node (ref "LM2917_8") (pin "1") (pinfunction "1_1") (pintype "passive"))
      (node (ref "R17") (pin "1") (pinfunction "1_1") (pintype "passive"))
      (node (ref "R22") (pin "2") (pinfunction "2_2") (pintype "passive"))
      (node (ref "R31") (pin "1") (pinfunction "1_1") (pintype "passive"))
      (node (ref "R32") (pin "1") (pinfunction "1_1") (pintype "passive"))
      (node (ref "R33") (pin "1") (pinfunction "1_1") (pintype "passive"))
      (node (ref "R38") (pin "1") (pinfunction "1_1") (pintype "passive"))
      (node (ref "U$1") (pin "2") (pinfunction "2_2") (pintype "passive"))
    )
    (net (code "43") (name "unconnected-(U$1-Pad4)") (class "Default")
      (node (ref "U$1") (pin "4") (pinfunction "4_4") (pintype "passive"))
    )
  )
)
